# HB-OU-MP3-LED_V1_2.net
KiCad netlist of a schematic drawn in EAGLE
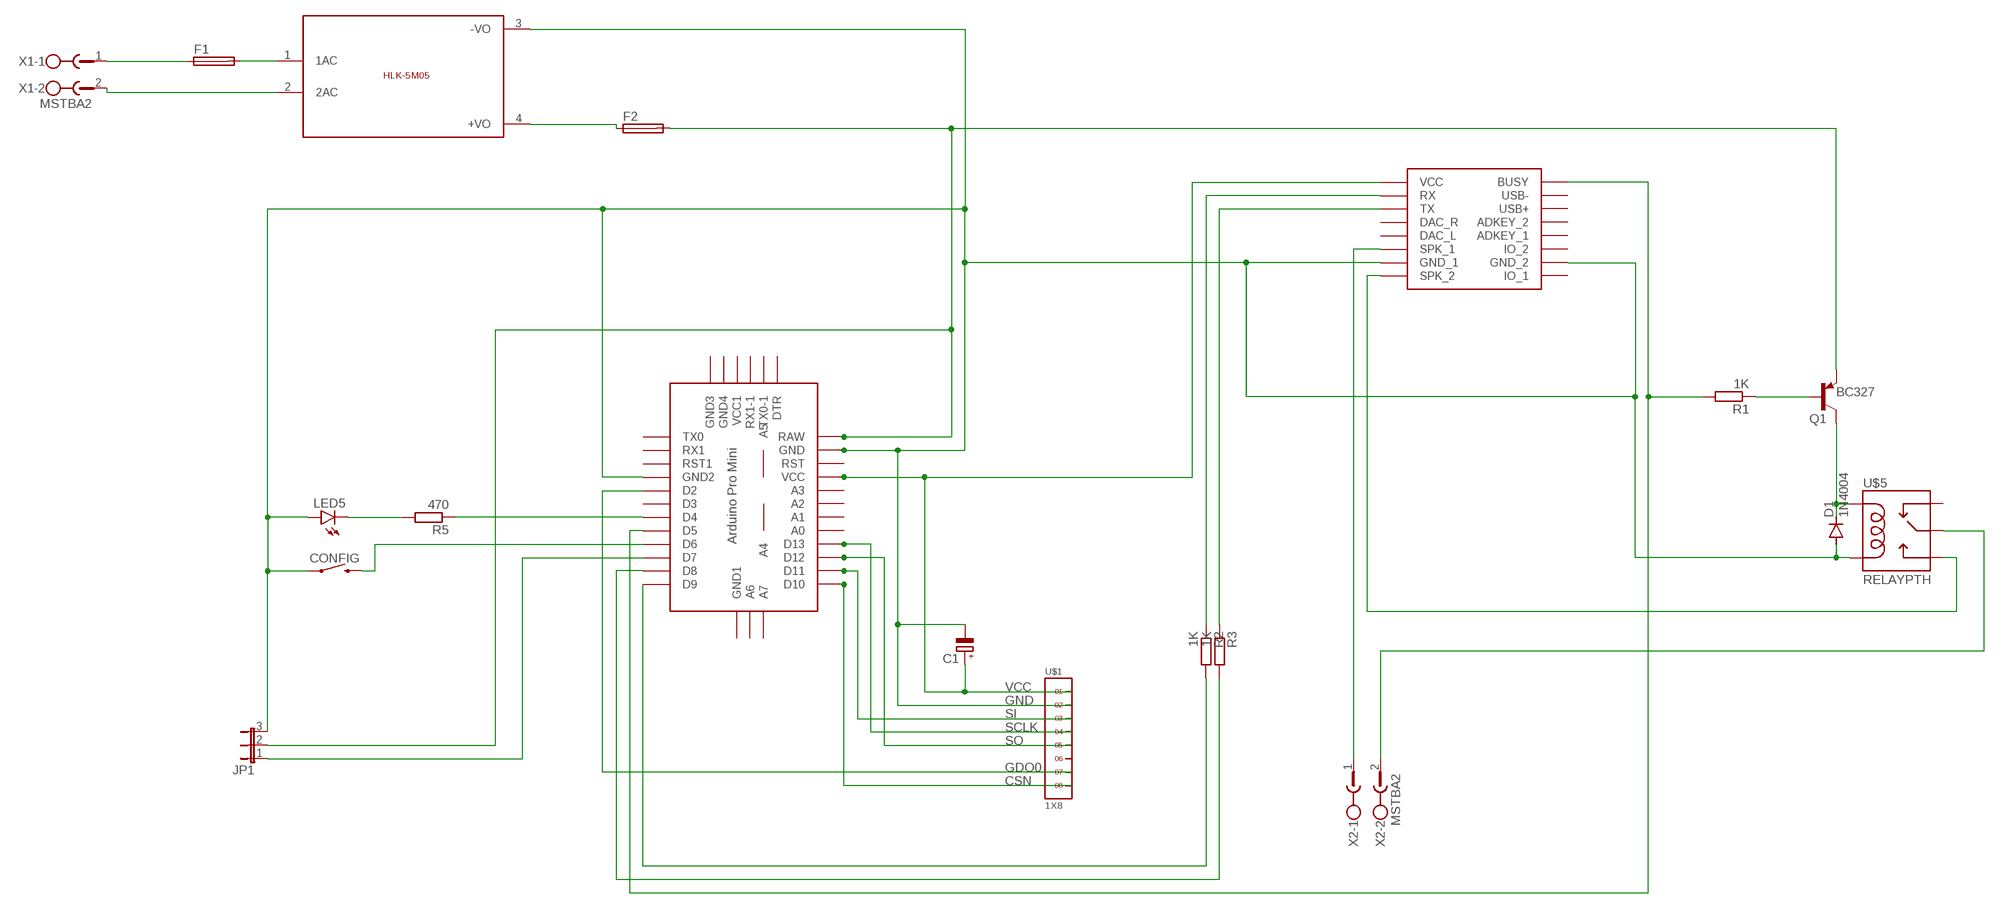
[diagram p0: schematic, sheet 1]

(export (version "E")
  (design (tool "Eeschema 10.0.6"))
  (components
    (comp (ref "C1")
      (value "CPOL-EUE2.5-5")
      (footprint "eagle-import:E2,5-5")
      (libsource (lib "eagle-import") (part "CPOL-EUE2.5-5"))
    )
    (comp (ref "CONFIG")
      (value "MOMENTARY-SWITCH-SPST-PTH-6.0MM-KIT")
      (footprint "eagle-import:TACTILE_SWITCH_PTH_6.0MM_KIT")
      (libsource (lib "eagle-import") (part "MOMENTARY-SWITCH-SPST-PTH-6.0MM-KIT"))
    )
    (comp (ref "D1")
      (value "1N4004")
      (footprint "eagle-import:DO41-10")
      (libsource (lib "eagle-import") (part "1N4004"))
    )
    (comp (ref "F1")
      (value "SH22,5A")
      (footprint "eagle-import:SH22,5A")
      (fields (field (name "MPN") "0031.7701.11"))
      (libsource (lib "eagle-import") (part "SH22,5A"))
    )
    (comp (ref "F2")
      (value "SH22,5A")
      (footprint "eagle-import:SH22,5A")
      (fields (field (name "MPN") "0031.7701.11"))
      (libsource (lib "eagle-import") (part "SH22,5A"))
    )
    (comp (ref "JP1")
      (value "JP2E")
      (footprint "eagle-import:JP2")
      (libsource (lib "eagle-import") (part "JP2E"))
    )
    (comp (ref "LED5")
      (value "LED3MM")
      (footprint "eagle-import:LED3MM")
      (libsource (lib "eagle-import") (part "LED3MM"))
    )
    (comp (ref "Q1")
      (value "BC327")
      (footprint "eagle-import:TO92")
      (libsource (lib "eagle-import") (part "BC327"))
    )
    (comp (ref "R1")
      (value "1K")
      (footprint "eagle-import:0309_10")
      (libsource (lib "eagle-import") (part "R-EU_0309/10"))
    )
    (comp (ref "R2")
      (value "1K")
      (footprint "eagle-import:0309_10")
      (libsource (lib "eagle-import") (part "R-EU_0309/10"))
    )
    (comp (ref "R3")
      (value "1K")
      (footprint "eagle-import:0309_10")
      (libsource (lib "eagle-import") (part "R-EU_0309/10"))
    )
    (comp (ref "R5")
      (value "470")
      (footprint "eagle-import:0309_10")
      (libsource (lib "eagle-import") (part "R-EU_0309/10"))
    )
    (comp (ref "U$1")
      (value "1X8")
      (footprint "eagle-import:1X8")
      (libsource (lib "eagle-import") (part "1X8"))
    )
    (comp (ref "U$2")
      (value "ABK-PRO-MINI")
      (footprint "eagle-import:ABK-PRO-MINI")
      (libsource (lib "eagle-import") (part "ABK-PRO-MINI"))
    )
    (comp (ref "U$3")
      (value "5VDC/5W")
      (footprint "eagle-import:HLK-5M05")
      (libsource (lib "eagle-import") (part "HLK-5M05"))
    )
    (comp (ref "U$4")
      (value "DFPLAYER")
      (footprint "eagle-import:DFPLAYER")
      (libsource (lib "eagle-import") (part "DFPLAYER"))
    )
    (comp (ref "U$5")
      (value "RELAYPTH")
      (footprint "eagle-import:SRD-05VDC-SL-C")
      (libsource (lib "eagle-import") (part "RELAYPTH"))
    )
    (comp (ref "X1")
      (value "MSTBA2")
      (footprint "eagle-import:MSTBA2")
      (fields (field (name "MF") "FARNELL") (field (name "MPN") "1757242"))
      (libsource (lib "eagle-import") (part "MSTBA2"))
    )
    (comp (ref "X2")
      (value "MSTBA2")
      (footprint "eagle-import:MSTBA2")
      (fields (field (name "MF") "FARNELL") (field (name "MPN") "1757242"))
      (libsource (lib "eagle-import") (part "MSTBA2"))
    )
  )
  (nets
    (net (code "1") (name "/CSN") (class "Default")
      (node (ref "U$1") (pin "8") (pinfunction "8_8") (pintype "bidirectional"))
      (node (ref "U$2") (pin "D10") (pinfunction "D10_D10") (pintype "bidirectional"))
    )
    (net (code "2") (name "/GDO0") (class "Default")
      (node (ref "U$1") (pin "7") (pinfunction "7_7") (pintype "bidirectional"))
      (node (ref "U$2") (pin "D2") (pinfunction "D2_D2") (pintype "bidirectional"))
    )
    (net (code "3") (name "/GND") (class "Default")
      (node (ref "C1") (pin "-") (pinfunction "-_-") (pintype "passive"))
      (node (ref "CONFIG") (pin "1") (pinfunction "1_1") (pintype "passive"))
      (node (ref "D1") (pin "A") (pinfunction "A_A") (pintype "passive"))
      (node (ref "JP1") (pin "3") (pinfunction "3_3") (pintype "passive"))
      (node (ref "LED5") (pin "A") (pinfunction "A_A") (pintype "passive"))
      (node (ref "U$1") (pin "2") (pinfunction "2_2") (pintype "bidirectional"))
      (node (ref "U$2") (pin "GND") (pinfunction "GND_GND") (pintype "bidirectional"))
      (node (ref "U$2") (pin "GND1") (pinfunction "GND2_GND1") (pintype "bidirectional"))
      (node (ref "U$3") (pin "3") (pinfunction "-VO_3") (pintype "bidirectional"))
      (node (ref "U$4") (pin "GND_1") (pinfunction "GND_1_GND_1") (pintype "bidirectional"))
      (node (ref "U$4") (pin "GND_2") (pinfunction "GND_2_GND_2") (pintype "bidirectional"))
      (node (ref "U$5") (pin "COIL0") (pinfunction "COIL0_COIL0") (pintype "bidirectional"))
    )
    (net (code "4") (name "/SCLK") (class "Default")
      (node (ref "U$1") (pin "4") (pinfunction "4_4") (pintype "bidirectional"))
      (node (ref "U$2") (pin "D13") (pinfunction "D13_D13") (pintype "bidirectional"))
    )
    (net (code "5") (name "/SI") (class "Default")
      (node (ref "U$1") (pin "3") (pinfunction "3_3") (pintype "bidirectional"))
      (node (ref "U$2") (pin "D11") (pinfunction "D11_D11") (pintype "bidirectional"))
    )
    (net (code "6") (name "/SO") (class "Default")
      (node (ref "U$1") (pin "5") (pinfunction "5_5") (pintype "bidirectional"))
      (node (ref "U$2") (pin "D12") (pinfunction "D12_D12") (pintype "bidirectional"))
    )
    (net (code "7") (name "/VCC") (class "Default")
      (node (ref "C1") (pin "+") (pinfunction "+_+") (pintype "passive"))
      (node (ref "U$1") (pin "1") (pinfunction "1_1") (pintype "bidirectional"))
      (node (ref "U$2") (pin "VCC") (pinfunction "VCC_VCC") (pintype "bidirectional"))
      (node (ref "U$4") (pin "VCC") (pinfunction "VCC_VCC") (pintype "bidirectional"))
    )
    (net (code "8") (name "Net-(CONFIG-2)") (class "Default")
      (node (ref "CONFIG") (pin "3") (pinfunction "2_3") (pintype "passive"))
      (node (ref "U$2") (pin "D6") (pinfunction "D6_D6") (pintype "bidirectional"))
    )
    (net (code "9") (name "Net-(F1-Pad1)") (class "Default")
      (node (ref "F1") (pin "1") (pinfunction "1_1") (pintype "passive"))
      (node (ref "X1") (pin "1") (pinfunction "1_1") (pintype "passive"))
    )
    (net (code "10") (name "Net-(JP1-Pad1)") (class "Default")
      (node (ref "JP1") (pin "1") (pinfunction "1_1") (pintype "passive"))
      (node (ref "U$2") (pin "D7") (pinfunction "D7_D7") (pintype "bidirectional"))
    )
    (net (code "11") (name "Net-(LED5-C)") (class "Default")
      (node (ref "LED5") (pin "K") (pinfunction "C_K") (pintype "passive"))
      (node (ref "R5") (pin "2") (pinfunction "2_2") (pintype "passive"))
    )
    (net (code "12") (name "Net-(Q1-B)") (class "Default")
      (node (ref "Q1") (pin "2") (pinfunction "B_2") (pintype "passive"))
      (node (ref "R1") (pin "1") (pinfunction "1_1") (pintype "passive"))
    )
    (net (code "13") (name "Net-(Q1-C)") (class "Default")
      (node (ref "D1") (pin "C") (pinfunction "C_C") (pintype "passive"))
      (node (ref "Q1") (pin "3") (pinfunction "C_3") (pintype "passive"))
      (node (ref "U$5") (pin "COIL1") (pinfunction "COIL1_COIL1") (pintype "bidirectional"))
    )
    (net (code "14") (name "Net-(Q1-E)") (class "Default")
      (node (ref "F2") (pin "2") (pinfunction "2_2") (pintype "passive"))
      (node (ref "JP1") (pin "2") (pinfunction "2_2") (pintype "passive"))
      (node (ref "Q1") (pin "1") (pinfunction "E_1") (pintype "passive"))
      (node (ref "U$2") (pin "RAW") (pinfunction "RAW_RAW") (pintype "bidirectional"))
    )
    (net (code "15") (name "Net-(R1-Pad2)") (class "Default")
      (node (ref "R1") (pin "2") (pinfunction "2_2") (pintype "passive"))
      (node (ref "U$2") (pin "D5") (pinfunction "D5_D5") (pintype "bidirectional"))
      (node (ref "U$4") (pin "BUSY") (pinfunction "BUSY_BUSY") (pintype "bidirectional"))
    )
    (net (code "16") (name "Net-(R2-Pad1)") (class "Default")
      (node (ref "R2") (pin "1") (pinfunction "1_1") (pintype "passive"))
      (node (ref "U$4") (pin "RX") (pinfunction "RX_RX") (pintype "bidirectional"))
    )
    (net (code "17") (name "Net-(R2-Pad2)") (class "Default")
      (node (ref "R2") (pin "2") (pinfunction "2_2") (pintype "passive"))
      (node (ref "U$2") (pin "D9") (pinfunction "D9_D9") (pintype "bidirectional"))
    )
    (net (code "18") (name "Net-(R3-Pad1)") (class "Default")
      (node (ref "R3") (pin "1") (pinfunction "1_1") (pintype "passive"))
      (node (ref "U$4") (pin "TX") (pinfunction "TX_TX") (pintype "bidirectional"))
    )
    (net (code "19") (name "Net-(R3-Pad2)") (class "Default")
      (node (ref "R3") (pin "2") (pinfunction "2_2") (pintype "passive"))
      (node (ref "U$2") (pin "D8") (pinfunction "D8_D8") (pintype "bidirectional"))
    )
    (net (code "20") (name "Net-(R5-Pad1)") (class "Default")
      (node (ref "R5") (pin "1") (pinfunction "1_1") (pintype "passive"))
      (node (ref "U$2") (pin "D4") (pinfunction "D4_D4") (pintype "bidirectional"))
    )
    (net (code "21") (name "Net-(U$3-+VO)") (class "Default")
      (node (ref "F2") (pin "1") (pinfunction "1_1") (pintype "passive"))
      (node (ref "U$3") (pin "4") (pinfunction "+VO_4") (pintype "bidirectional"))
    )
    (net (code "22") (name "Net-(U$3-1AC)") (class "Default")
      (node (ref "F1") (pin "2") (pinfunction "2_2") (pintype "passive"))
      (node (ref "U$3") (pin "1") (pinfunction "1AC_1") (pintype "bidirectional"))
    )
    (net (code "23") (name "Net-(U$3-2AC)") (class "Default")
      (node (ref "U$3") (pin "2") (pinfunction "2AC_2") (pintype "bidirectional"))
      (node (ref "X1") (pin "2") (pinfunction "1_2") (pintype "passive"))
    )
    (net (code "24") (name "Net-(U$4-SPK_1)") (class "Default")
      (node (ref "U$4") (pin "SPK1") (pinfunction "SPK_1_SPK1") (pintype "bidirectional"))
      (node (ref "X2") (pin "1") (pinfunction "1_1") (pintype "passive"))
    )
    (net (code "25") (name "Net-(U$4-SPK_2)") (class "Default")
      (node (ref "U$4") (pin "SPK2") (pinfunction "SPK_2_SPK2") (pintype "bidirectional"))
      (node (ref "U$5") (pin "SWOPEN") (pinfunction "SWOPEN_SWOPEN") (pintype "bidirectional"))
    )
    (net (code "26") (name "Net-(X2B-1)") (class "Default")
      (node (ref "U$5") (pin "SWCOMMON") (pinfunction "SWCOMMON_SWCOMMON") (pintype "bidirectional"))
      (node (ref "X2") (pin "2") (pinfunction "1_2") (pintype "passive"))
    )
    (net (code "27") (name "unconnected-(U$1-Pad6)") (class "Default")
      (node (ref "U$1") (pin "6") (pinfunction "6_6") (pintype "bidirectional"))
    )
    (net (code "28") (name "unconnected-(U$2-GND1-PadGND4)") (class "Default")
      (node (ref "U$2") (pin "GND4") (pinfunction "GND1_GND4") (pintype "bidirectional"))
    )
    (net (code "29") (name "unconnected-(U$2-GND3-PadGND2)") (class "Default")
      (node (ref "U$2") (pin "GND2") (pinfunction "GND3_GND2") (pintype "bidirectional"))
    )
    (net (code "30") (name "unconnected-(U$2-GND4-PadGND3)") (class "Default")
      (node (ref "U$2") (pin "GND3") (pinfunction "GND4_GND3") (pintype "bidirectional"))
    )
    (net (code "31") (name "unconnected-(U$2-PadA0)") (class "Default")
      (node (ref "U$2") (pin "A0") (pinfunction "A0_A0") (pintype "bidirectional"))
    )
    (net (code "32") (name "unconnected-(U$2-PadA1)") (class "Default")
      (node (ref "U$2") (pin "A1") (pinfunction "A1_A1") (pintype "bidirectional"))
    )
    (net (code "33") (name "unconnected-(U$2-PadA2)") (class "Default")
      (node (ref "U$2") (pin "A2") (pinfunction "A2_A2") (pintype "bidirectional"))
    )
    (net (code "34") (name "unconnected-(U$2-PadA3)") (class "Default")
      (node (ref "U$2") (pin "A3") (pinfunction "A3_A3") (pintype "bidirectional"))
    )
    (net (code "35") (name "unconnected-(U$2-PadA4)") (class "Default")
      (node (ref "U$2") (pin "A4") (pinfunction "A4_A4") (pintype "bidirectional"))
    )
    (net (code "36") (name "unconnected-(U$2-PadA5)") (class "Default")
      (node (ref "U$2") (pin "A5") (pinfunction "A5_A5") (pintype "bidirectional"))
    )
    (net (code "37") (name "unconnected-(U$2-PadA6)") (class "Default")
      (node (ref "U$2") (pin "A6") (pinfunction "A6_A6") (pintype "bidirectional"))
    )
    (net (code "38") (name "unconnected-(U$2-PadA7)") (class "Default")
      (node (ref "U$2") (pin "A7") (pinfunction "A7_A7") (pintype "bidirectional"))
    )
    (net (code "39") (name "unconnected-(U$2-PadD3)") (class "Default")
      (node (ref "U$2") (pin "D3") (pinfunction "D3_D3") (pintype "bidirectional"))
    )
    (net (code "40") (name "unconnected-(U$2-PadDTR)") (class "Default")
      (node (ref "U$2") (pin "DTR") (pinfunction "DTR_DTR") (pintype "bidirectional"))
    )
    (net (code "41") (name "unconnected-(U$2-PadRST)") (class "Default")
      (node (ref "U$2") (pin "RST") (pinfunction "RST_RST") (pintype "bidirectional"))
    )
    (net (code "42") (name "unconnected-(U$2-PadRST1)") (class "Default")
      (node (ref "U$2") (pin "RST1") (pinfunction "RST1_RST1") (pintype "bidirectional"))
    )
    (net (code "43") (name "unconnected-(U$2-PadRX1)") (class "Default")
      (node (ref "U$2") (pin "RX1") (pinfunction "RX1_RX1") (pintype "bidirectional"))
    )
    (net (code "44") (name "unconnected-(U$2-PadRX1-1)") (class "Default")
      (node (ref "U$2") (pin "RX1-1") (pinfunction "RX1-1_RX1-1") (pintype "bidirectional"))
    )
    (net (code "45") (name "unconnected-(U$2-PadTX0)") (class "Default")
      (node (ref "U$2") (pin "TX0") (pinfunction "TX0_TX0") (pintype "bidirectional"))
    )
    (net (code "46") (name "unconnected-(U$2-PadTX0-1)") (class "Default")
      (node (ref "U$2") (pin "TX0-1") (pinfunction "TX0-1_TX0-1") (pintype "bidirectional"))
    )
    (net (code "47") (name "unconnected-(U$2-PadVCC1)") (class "Default")
      (node (ref "U$2") (pin "VCC1") (pinfunction "VCC1_VCC1") (pintype "bidirectional"))
    )
    (net (code "48") (name "unconnected-(U$4-ADKEY_1-PadADKEY1)") (class "Default")
      (node (ref "U$4") (pin "ADKEY1") (pinfunction "ADKEY_1_ADKEY1") (pintype "bidirectional"))
    )
    (net (code "49") (name "unconnected-(U$4-ADKEY_2-PadADKEY2)") (class "Default")
      (node (ref "U$4") (pin "ADKEY2") (pinfunction "ADKEY_2_ADKEY2") (pintype "bidirectional"))
    )
    (net (code "50") (name "unconnected-(U$4-IO_1-PadIO1)") (class "Default")
      (node (ref "U$4") (pin "IO1") (pinfunction "IO_1_IO1") (pintype "bidirectional"))
    )
    (net (code "51") (name "unconnected-(U$4-IO_2-PadIO2)") (class "Default")
      (node (ref "U$4") (pin "IO2") (pinfunction "IO_2_IO2") (pintype "bidirectional"))
    )
    (net (code "52") (name "unconnected-(U$4-PadDAC_L)") (class "Default")
      (node (ref "U$4") (pin "DAC_L") (pinfunction "DAC_L_DAC_L") (pintype "bidirectional"))
    )
    (net (code "53") (name "unconnected-(U$4-PadDAC_R)") (class "Default")
      (node (ref "U$4") (pin "DAC_R") (pinfunction "DAC_R_DAC_R") (pintype "bidirectional"))
    )
    (net (code "54") (name "unconnected-(U$4-PadUSB+)") (class "Default")
      (node (ref "U$4") (pin "USB+") (pinfunction "USB+_USB+") (pintype "bidirectional"))
    )
    (net (code "55") (name "unconnected-(U$4-PadUSB-)") (class "Default")
      (node (ref "U$4") (pin "USB-") (pinfunction "USB-_USB-") (pintype "bidirectional"))
    )
    (net (code "56") (name "unconnected-(U$5-SWCLOSE-PadSWCLOSED)") (class "Default")
      (node (ref "U$5") (pin "SWCLOSED") (pinfunction "SWCLOSE_SWCLOSED") (pintype "bidirectional"))
    )
  )
)
